# ShiftRegisterSensor.net
KiCad netlist of a schematic drawn in Altium Designer
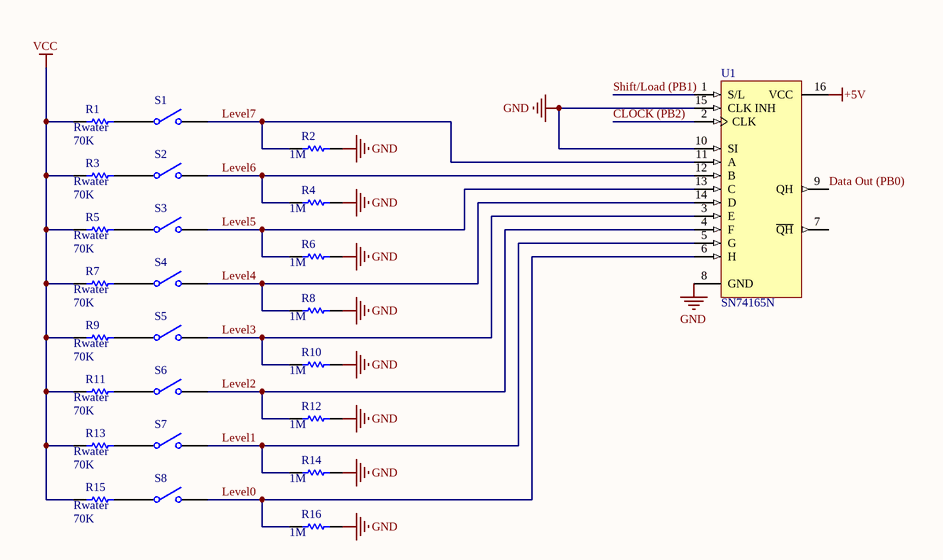
[diagram p0: ShiftRegisterSensor.SchDoc]

(export (version "E")
  (design (tool "Eeschema 10.0.6"))
  (components
    (comp (ref "R1")
      (value "Rwater")
      (footprint "AXIAL-0.3")
      (description "Resistor")
      (fields (field (name "ALTIUM_VALUE") "70K") (field (name "PUBLISHER") "Altium Limited"))
      (libsource (lib "Miscellaneous Devices") (part "Res1"))
    )
    (comp (ref "R2")
      (value "1M")
      (footprint "AXIAL-0.3")
      (description "Resistor")
      (fields (field (name "Comment") "Res1") (field (name "PUBLISHER") "Altium Limited"))
      (libsource (lib "Miscellaneous Devices") (part "Res1"))
    )
    (comp (ref "R3")
      (value "Rwater")
      (footprint "AXIAL-0.3")
      (description "Resistor")
      (fields (field (name "ALTIUM_VALUE") "70K") (field (name "PUBLISHER") "Altium Limited"))
      (libsource (lib "Miscellaneous Devices") (part "Res1"))
    )
    (comp (ref "R4")
      (value "1M")
      (footprint "AXIAL-0.3")
      (description "Resistor")
      (fields (field (name "Comment") "Res1") (field (name "PUBLISHER") "Altium Limited"))
      (libsource (lib "Miscellaneous Devices") (part "Res1"))
    )
    (comp (ref "R5")
      (value "Rwater")
      (footprint "AXIAL-0.3")
      (description "Resistor")
      (fields (field (name "ALTIUM_VALUE") "70K") (field (name "PUBLISHER") "Altium Limited"))
      (libsource (lib "Miscellaneous Devices") (part "Res1"))
    )
    (comp (ref "R6")
      (value "1M")
      (footprint "AXIAL-0.3")
      (description "Resistor")
      (fields (field (name "Comment") "Res1") (field (name "PUBLISHER") "Altium Limited"))
      (libsource (lib "Miscellaneous Devices") (part "Res1"))
    )
    (comp (ref "R7")
      (value "Rwater")
      (footprint "AXIAL-0.3")
      (description "Resistor")
      (fields (field (name "ALTIUM_VALUE") "70K") (field (name "PUBLISHER") "Altium Limited"))
      (libsource (lib "Miscellaneous Devices") (part "Res1"))
    )
    (comp (ref "R8")
      (value "1M")
      (footprint "AXIAL-0.3")
      (description "Resistor")
      (fields (field (name "Comment") "Res1") (field (name "PUBLISHER") "Altium Limited"))
      (libsource (lib "Miscellaneous Devices") (part "Res1"))
    )
    (comp (ref "R9")
      (value "Rwater")
      (footprint "AXIAL-0.3")
      (description "Resistor")
      (fields (field (name "ALTIUM_VALUE") "70K") (field (name "PUBLISHER") "Altium Limited"))
      (libsource (lib "Miscellaneous Devices") (part "Res1"))
    )
    (comp (ref "R10")
      (value "1M")
      (footprint "AXIAL-0.3")
      (description "Resistor")
      (fields (field (name "Comment") "Res1") (field (name "PUBLISHER") "Altium Limited"))
      (libsource (lib "Miscellaneous Devices") (part "Res1"))
    )
    (comp (ref "R11")
      (value "Rwater")
      (footprint "AXIAL-0.3")
      (description "Resistor")
      (fields (field (name "ALTIUM_VALUE") "70K") (field (name "PUBLISHER") "Altium Limited"))
      (libsource (lib "Miscellaneous Devices") (part "Res1"))
    )
    (comp (ref "R12")
      (value "1M")
      (footprint "AXIAL-0.3")
      (description "Resistor")
      (fields (field (name "Comment") "Res1") (field (name "PUBLISHER") "Altium Limited"))
      (libsource (lib "Miscellaneous Devices") (part "Res1"))
    )
    (comp (ref "R13")
      (value "Rwater")
      (footprint "AXIAL-0.3")
      (description "Resistor")
      (fields (field (name "ALTIUM_VALUE") "70K") (field (name "PUBLISHER") "Altium Limited"))
      (libsource (lib "Miscellaneous Devices") (part "Res1"))
    )
    (comp (ref "R14")
      (value "1M")
      (footprint "AXIAL-0.3")
      (description "Resistor")
      (fields (field (name "Comment") "Res1") (field (name "PUBLISHER") "Altium Limited"))
      (libsource (lib "Miscellaneous Devices") (part "Res1"))
    )
    (comp (ref "R15")
      (value "Rwater")
      (footprint "AXIAL-0.3")
      (description "Resistor")
      (fields (field (name "ALTIUM_VALUE") "70K") (field (name "PUBLISHER") "Altium Limited"))
      (libsource (lib "Miscellaneous Devices") (part "Res1"))
    )
    (comp (ref "R16")
      (value "1M")
      (footprint "AXIAL-0.3")
      (description "Resistor")
      (fields (field (name "Comment") "Res1") (field (name "PUBLISHER") "Altium Limited"))
      (libsource (lib "Miscellaneous Devices") (part "Res1"))
    )
    (comp (ref "S1")
      (value "SW-SPST")
      (footprint "SPST-2")
      (description "Single-Pole, Single-Throw Switch")
      (fields (field (name "PUBLISHER") "Altium Limited"))
      (libsource (lib "Miscellaneous Devices") (part "SW-SPST"))
    )
    (comp (ref "S2")
      (value "SW-SPST")
      (footprint "SPST-2")
      (description "Single-Pole, Single-Throw Switch")
      (fields (field (name "PUBLISHER") "Altium Limited"))
      (libsource (lib "Miscellaneous Devices") (part "SW-SPST"))
    )
    (comp (ref "S3")
      (value "SW-SPST")
      (footprint "SPST-2")
      (description "Single-Pole, Single-Throw Switch")
      (fields (field (name "PUBLISHER") "Altium Limited"))
      (libsource (lib "Miscellaneous Devices") (part "SW-SPST"))
    )
    (comp (ref "S4")
      (value "SW-SPST")
      (footprint "SPST-2")
      (description "Single-Pole, Single-Throw Switch")
      (fields (field (name "PUBLISHER") "Altium Limited"))
      (libsource (lib "Miscellaneous Devices") (part "SW-SPST"))
    )
    (comp (ref "S5")
      (value "SW-SPST")
      (footprint "SPST-2")
      (description "Single-Pole, Single-Throw Switch")
      (fields (field (name "PUBLISHER") "Altium Limited"))
      (libsource (lib "Miscellaneous Devices") (part "SW-SPST"))
    )
    (comp (ref "S6")
      (value "SW-SPST")
      (footprint "SPST-2")
      (description "Single-Pole, Single-Throw Switch")
      (fields (field (name "PUBLISHER") "Altium Limited"))
      (libsource (lib "Miscellaneous Devices") (part "SW-SPST"))
    )
    (comp (ref "S7")
      (value "SW-SPST")
      (footprint "SPST-2")
      (description "Single-Pole, Single-Throw Switch")
      (fields (field (name "PUBLISHER") "Altium Limited"))
      (libsource (lib "Miscellaneous Devices") (part "SW-SPST"))
    )
    (comp (ref "S8")
      (value "SW-SPST")
      (footprint "SPST-2")
      (description "Single-Pole, Single-Throw Switch")
      (fields (field (name "PUBLISHER") "Altium Limited"))
      (libsource (lib "Miscellaneous Devices") (part "SW-SPST"))
    )
    (comp (ref "U1")
      (value "SN74165N")
      (footprint "DIP-16/X1.5")
      (description "Parallel-Load 8-Bit Shift Register")
      (fields
        (field (name "MANUFACTURER") "Texas Instruments")
        (field (name "PUBLISHER") "Altium Hobart Technology Centre")
      )
      (libsource (lib "TI Logic Register") (part "SN74165N"))
    )
  )
  (nets
    (net (code "1") (name "+5V") (class "Default")
      (node (ref "U1") (pin "16") (pinfunction "VCC_16") (pintype "power_in"))
    )
    (net (code "2") (name "/CLOCK (PB2)") (class "Default")
      (node (ref "U1") (pin "2") (pinfunction "CLK_2") (pintype "input"))
    )
    (net (code "3") (name "/Data Out (PB0)") (class "Default")
      (node (ref "U1") (pin "9") (pinfunction "QH_9") (pintype "output"))
    )
    (net (code "4") (name "/Level0") (class "Default")
      (node (ref "R16") (pin "1") (pinfunction "1_1") (pintype "passive"))
      (node (ref "S8") (pin "2") (pinfunction "NO_2") (pintype "passive"))
      (node (ref "U1") (pin "6") (pinfunction "H_6") (pintype "input"))
    )
    (net (code "5") (name "/Level1") (class "Default")
      (node (ref "R14") (pin "1") (pinfunction "1_1") (pintype "passive"))
      (node (ref "S7") (pin "2") (pinfunction "NO_2") (pintype "passive"))
      (node (ref "U1") (pin "5") (pinfunction "G_5") (pintype "input"))
    )
    (net (code "6") (name "/Level2") (class "Default")
      (node (ref "R12") (pin "1") (pinfunction "1_1") (pintype "passive"))
      (node (ref "S6") (pin "2") (pinfunction "NO_2") (pintype "passive"))
      (node (ref "U1") (pin "4") (pinfunction "F_4") (pintype "input"))
    )
    (net (code "7") (name "/Level3") (class "Default")
      (node (ref "R10") (pin "1") (pinfunction "1_1") (pintype "passive"))
      (node (ref "S5") (pin "2") (pinfunction "NO_2") (pintype "passive"))
      (node (ref "U1") (pin "3") (pinfunction "E_3") (pintype "input"))
    )
    (net (code "8") (name "/Level4") (class "Default")
      (node (ref "R8") (pin "1") (pinfunction "1_1") (pintype "passive"))
      (node (ref "S4") (pin "2") (pinfunction "NO_2") (pintype "passive"))
      (node (ref "U1") (pin "14") (pinfunction "D_14") (pintype "input"))
    )
    (net (code "9") (name "/Level5") (class "Default")
      (node (ref "R6") (pin "1") (pinfunction "1_1") (pintype "passive"))
      (node (ref "S3") (pin "2") (pinfunction "NO_2") (pintype "passive"))
      (node (ref "U1") (pin "13") (pinfunction "C_13") (pintype "input"))
    )
    (net (code "10") (name "/Level6") (class "Default")
      (node (ref "R4") (pin "1") (pinfunction "1_1") (pintype "passive"))
      (node (ref "S2") (pin "2") (pinfunction "NO_2") (pintype "passive"))
      (node (ref "U1") (pin "12") (pinfunction "B_12") (pintype "input"))
    )
    (net (code "11") (name "/Level7") (class "Default")
      (node (ref "R2") (pin "1") (pinfunction "1_1") (pintype "passive"))
      (node (ref "S1") (pin "2") (pinfunction "NO_2") (pintype "passive"))
      (node (ref "U1") (pin "11") (pinfunction "A_11") (pintype "input"))
    )
    (net (code "12") (name "/Shift{slash}Load (PB1)") (class "Default")
      (node (ref "U1") (pin "1") (pinfunction "S/L_1") (pintype "input"))
    )
    (net (code "13") (name "GND") (class "Default")
      (node (ref "R10") (pin "2") (pinfunction "2_2") (pintype "passive"))
      (node (ref "R12") (pin "2") (pinfunction "2_2") (pintype "passive"))
      (node (ref "R14") (pin "2") (pinfunction "2_2") (pintype "passive"))
      (node (ref "R16") (pin "2") (pinfunction "2_2") (pintype "passive"))
      (node (ref "R2") (pin "2") (pinfunction "2_2") (pintype "passive"))
      (node (ref "R4") (pin "2") (pinfunction "2_2") (pintype "passive"))
      (node (ref "R6") (pin "2") (pinfunction "2_2") (pintype "passive"))
      (node (ref "R8") (pin "2") (pinfunction "2_2") (pintype "passive"))
      (node (ref "U1") (pin "10") (pinfunction "SI_10") (pintype "input"))
      (node (ref "U1") (pin "15") (pinfunction "CLK_INH_15") (pintype "input"))
      (node (ref "U1") (pin "8") (pinfunction "GND_8") (pintype "power_in"))
    )
    (net (code "14") (name "Net-(S1-COMMON)") (class "Default")
      (node (ref "R1") (pin "2") (pinfunction "2_2") (pintype "passive"))
      (node (ref "S1") (pin "1") (pinfunction "COMMON_1") (pintype "passive"))
    )
    (net (code "15") (name "Net-(S2-COMMON)") (class "Default")
      (node (ref "R3") (pin "2") (pinfunction "2_2") (pintype "passive"))
      (node (ref "S2") (pin "1") (pinfunction "COMMON_1") (pintype "passive"))
    )
    (net (code "16") (name "Net-(S3-COMMON)") (class "Default")
      (node (ref "R5") (pin "2") (pinfunction "2_2") (pintype "passive"))
      (node (ref "S3") (pin "1") (pinfunction "COMMON_1") (pintype "passive"))
    )
    (net (code "17") (name "Net-(S4-COMMON)") (class "Default")
      (node (ref "R7") (pin "2") (pinfunction "2_2") (pintype "passive"))
      (node (ref "S4") (pin "1") (pinfunction "COMMON_1") (pintype "passive"))
    )
    (net (code "18") (name "Net-(S5-COMMON)") (class "Default")
      (node (ref "R9") (pin "2") (pinfunction "2_2") (pintype "passive"))
      (node (ref "S5") (pin "1") (pinfunction "COMMON_1") (pintype "passive"))
    )
    (net (code "19") (name "Net-(S6-COMMON)") (class "Default")
      (node (ref "R11") (pin "2") (pinfunction "2_2") (pintype "passive"))
      (node (ref "S6") (pin "1") (pinfunction "COMMON_1") (pintype "passive"))
    )
    (net (code "20") (name "Net-(S7-COMMON)") (class "Default")
      (node (ref "R13") (pin "2") (pinfunction "2_2") (pintype "passive"))
      (node (ref "S7") (pin "1") (pinfunction "COMMON_1") (pintype "passive"))
    )
    (net (code "21") (name "Net-(S8-COMMON)") (class "Default")
      (node (ref "R15") (pin "2") (pinfunction "2_2") (pintype "passive"))
      (node (ref "S8") (pin "1") (pinfunction "COMMON_1") (pintype "passive"))
    )
    (net (code "22") (name "VCC") (class "Default")
      (node (ref "R1") (pin "1") (pinfunction "1_1") (pintype "passive"))
      (node (ref "R11") (pin "1") (pinfunction "1_1") (pintype "passive"))
      (node (ref "R13") (pin "1") (pinfunction "1_1") (pintype "passive"))
      (node (ref "R15") (pin "1") (pinfunction "1_1") (pintype "passive"))
      (node (ref "R3") (pin "1") (pinfunction "1_1") (pintype "passive"))
      (node (ref "R5") (pin "1") (pinfunction "1_1") (pintype "passive"))
      (node (ref "R7") (pin "1") (pinfunction "1_1") (pintype "passive"))
      (node (ref "R9") (pin "1") (pinfunction "1_1") (pintype "passive"))
    )
    (net (code "23") (name "unconnected-(U1-~{QH}-Pad7)") (class "Default")
      (node (ref "U1") (pin "7") (pinfunction "~{QH}_7") (pintype "output"))
    )
  )
)
